# BaseBoard.net
KiCad netlist of a schematic drawn in Altium Designer
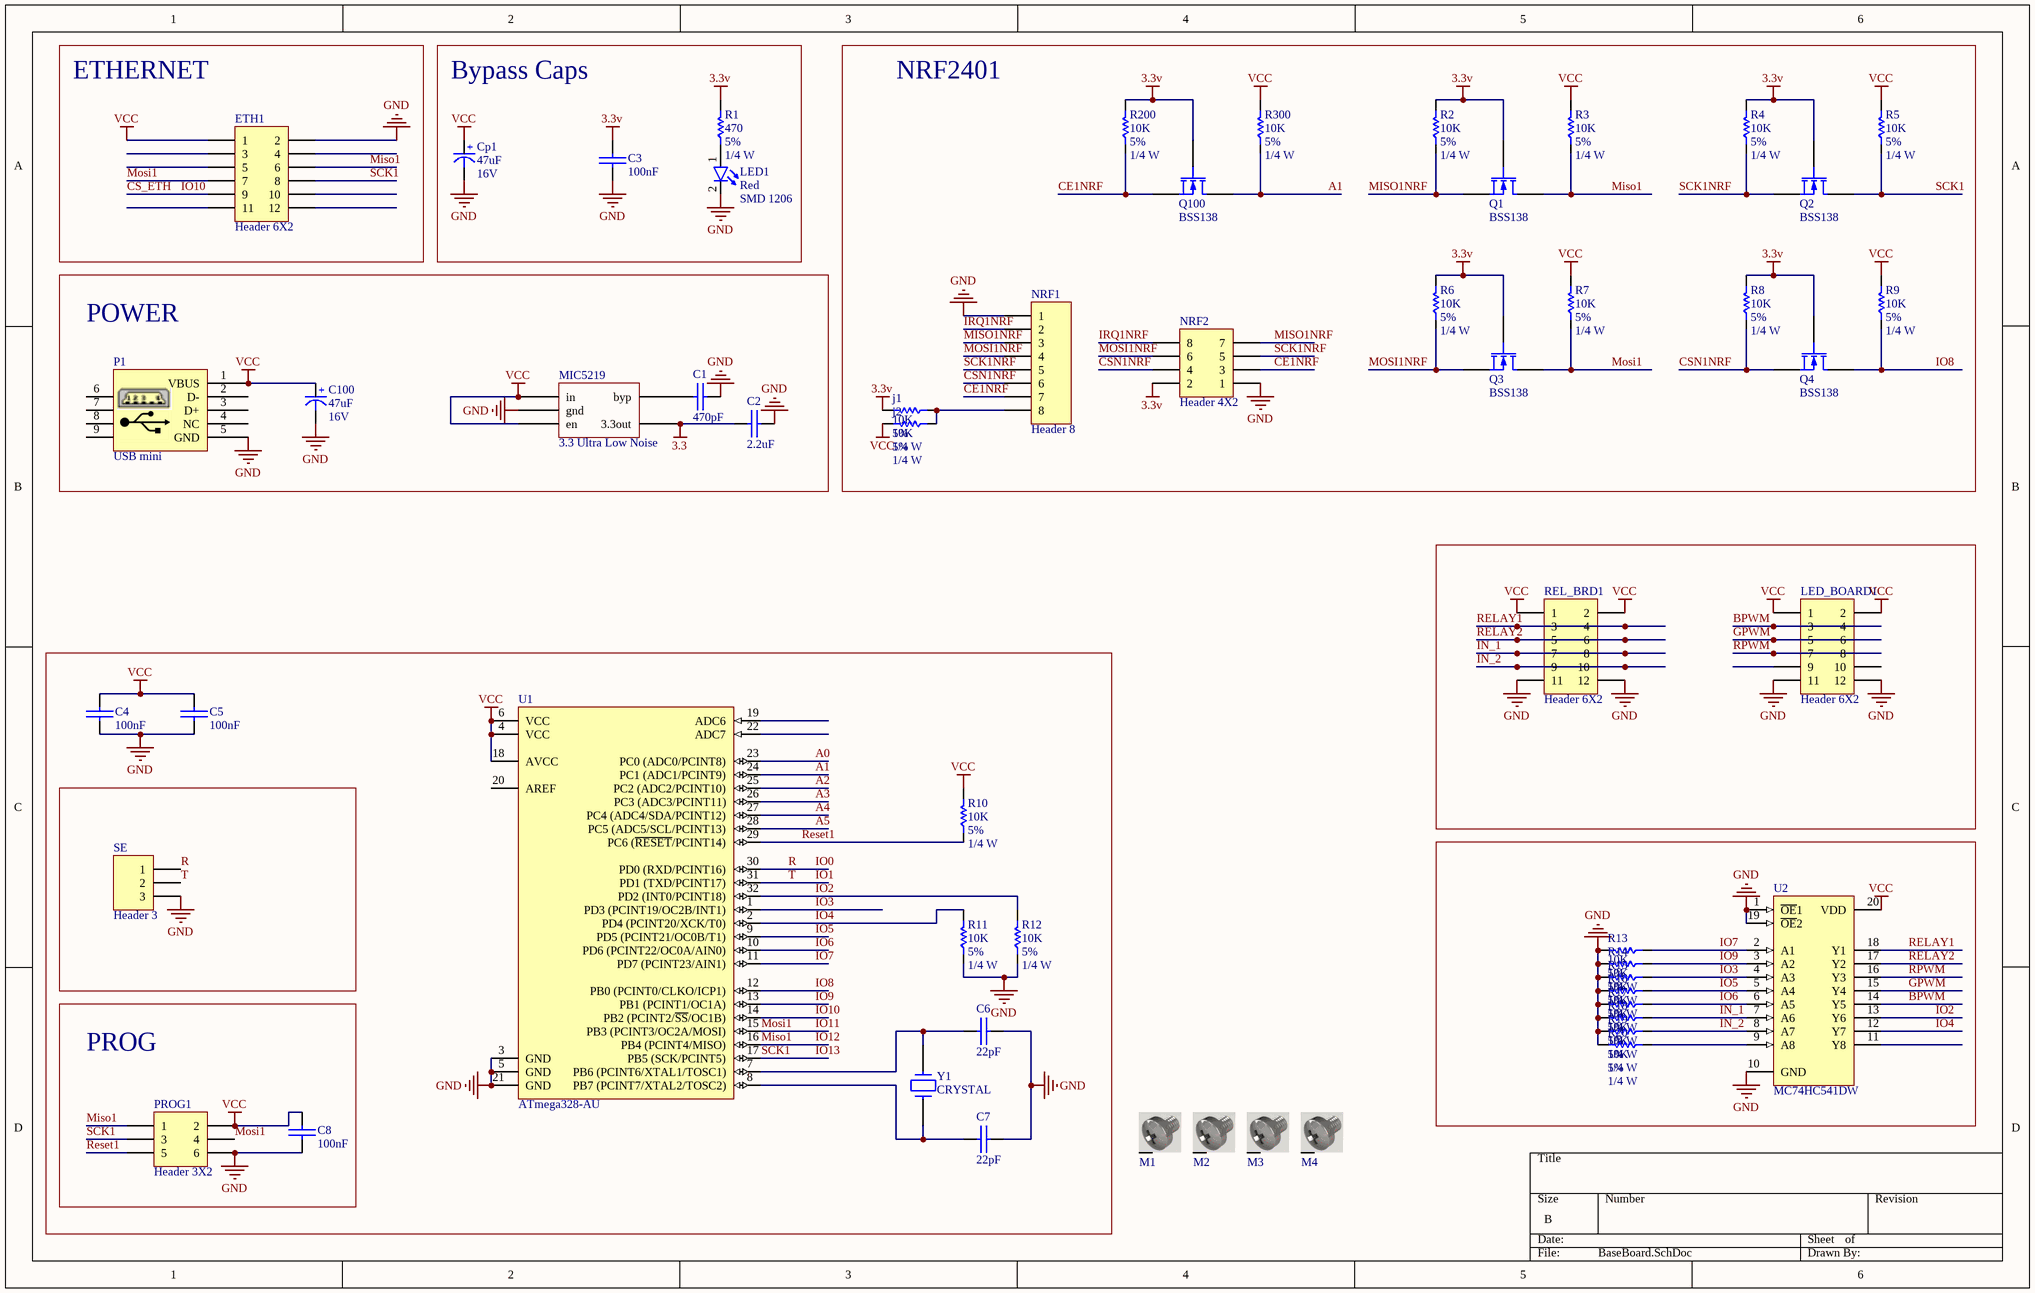
[diagram p0: BaseBoard.SchDoc]

(export (version "E")
  (design (tool "Eeschema 10.0.6"))
  (components
    (comp (ref "C1")
      (value "470pF")
      (footprint "SMD_CAP_0805")
      (description "Bipolar Capacitor")
      (fields (field (name "VOLTAGE") "100V") (field (name "DESIGNER") "Saeid Jorablo"))
      (libsource (lib "My Library") (part "Cap-Bipolar"))
    )
    (comp (ref "C2")
      (value "2.2uF")
      (footprint "SMD_CAP_1206")
      (description "Bipolar Capacitor")
      (fields (field (name "VOLTAGE") "100V") (field (name "DESIGNER") "Saeid Jorablo"))
      (libsource (lib "My Library") (part "Cap-Bipolar"))
    )
    (comp (ref "C3")
      (value "100nF")
      (footprint "CAPP 1206 (3216X18L) Size A")
      (description "Bipolar Capacitor")
      (fields (field (name "VOLTAGE") "100V") (field (name "DESIGNER") "Saeid Jorablo"))
      (libsource (lib "My Library") (part "Cap-Bipolar"))
    )
    (comp (ref "C4")
      (value "100nF")
      (footprint "CAPP 1206 (3216X18L) Size A")
      (description "Bipolar Capacitor")
      (fields (field (name "VOLTAGE") "100V") (field (name "DESIGNER") "Saeid Jorablo"))
      (libsource (lib "My Library") (part "Cap-Bipolar"))
    )
    (comp (ref "C5")
      (value "100nF")
      (footprint "CAPP 1206 (3216X18L) Size A")
      (description "Bipolar Capacitor")
      (fields (field (name "VOLTAGE") "100V") (field (name "DESIGNER") "Saeid Jorablo"))
      (libsource (lib "My Library") (part "Cap-Bipolar"))
    )
    (comp (ref "C6")
      (value "22pF")
      (footprint "CAPP 1206 (3216X18L) Size A")
      (description "Bipolar Capacitor")
      (fields (field (name "VOLTAGE") "100V") (field (name "DESIGNER") "Saeid Jorablo"))
      (libsource (lib "My Library") (part "Cap-Bipolar"))
    )
    (comp (ref "C7")
      (value "22pF")
      (footprint "CAPP 1206 (3216X18L) Size A")
      (description "Bipolar Capacitor")
      (fields (field (name "VOLTAGE") "100V") (field (name "DESIGNER") "Saeid Jorablo"))
      (libsource (lib "My Library") (part "Cap-Bipolar"))
    )
    (comp (ref "C8")
      (value "100nF")
      (footprint "CAPP 1206 (3216X18L) Size A")
      (description "Bipolar Capacitor")
      (fields (field (name "VOLTAGE") "100V") (field (name "DESIGNER") "Saeid Jorablo"))
      (libsource (lib "My Library") (part "Cap-Bipolar"))
    )
    (comp (ref "C100")
      (value "47uF")
      (footprint "CAPP 1206 (3216X18L) Size A")
      (description "Polar Capacitor")
      (fields (field (name "VOLTAGE") "16V") (field (name "DESIGNER") "Saeid Jorablo"))
      (libsource (lib "My Library") (part "Cap-Polar"))
    )
    (comp (ref "Cp1")
      (value "47uF")
      (footprint "CAPP 1206 (3216X18L) Size A")
      (description "Polar Capacitor")
      (fields (field (name "VOLTAGE") "16V") (field (name "DESIGNER") "Saeid Jorablo"))
      (libsource (lib "My Library") (part "Cap-Polar"))
    )
    (comp (ref "ETH1")
      (value "Header 6X2")
      (footprint "HDR2X6")
      (description "Header, 6-Pin, Dual row")
      (fields (field (name "PUBLISHER") "Altium Limited"))
      (libsource (lib "Miscellaneous Connectors") (part "Header 6X2"))
    )
    (comp (ref "j1")
      (value "10K")
      (footprint "RES 1206 (3216X08L)")
      (description "Resistor")
      (fields (field (name "TOLERANCE") "5%") (field (name "POWER") "1/4 W"))
      (libsource (lib "My Library") (part "Resistor"))
    )
    (comp (ref "j2")
      (value "10K")
      (footprint "RES 1206 (3216X08L)")
      (description "Resistor")
      (fields (field (name "TOLERANCE") "5%") (field (name "POWER") "1/4 W"))
      (libsource (lib "My Library") (part "Resistor"))
    )
    (comp (ref "LED1")
      (value "Red")
      (footprint "LED SMD 1206")
      (description "LED")
      (fields
        (field (name "COLOR") "Red")
        (field (name "SIZE") "SMD 1206")
        (field (name "DESIGNER") "Saeid Jorablo")
      )
      (libsource (lib "My Library") (part "LED"))
    )
    (comp (ref "LED_BOARD1")
      (value "Header 6X2")
      (footprint "HDR2X6")
      (description "Header, 6-Pin, Dual row")
      (fields (field (name "PUBLISHER") "Altium Limited"))
      (libsource (lib "Miscellaneous Connectors") (part "Header 6X2"))
    )
    (comp (ref "M1")
      (value "Screw")
      (footprint "Board Screw_No Silk")
      (description "Board Screw With Spacer")
      (libsource (lib "My Library") (part "Board Screw"))
    )
    (comp (ref "M2")
      (value "Screw")
      (footprint "Board Screw_No Silk")
      (description "Board Screw With Spacer")
      (libsource (lib "My Library") (part "Board Screw"))
    )
    (comp (ref "M3")
      (value "Screw")
      (footprint "Board Screw_No Silk")
      (description "Board Screw With Spacer")
      (libsource (lib "My Library") (part "Board Screw"))
    )
    (comp (ref "M4")
      (value "Screw")
      (footprint "Board Screw_No Silk")
      (description "Board Screw With Spacer")
      (libsource (lib "My Library") (part "Board Screw"))
    )
    (comp (ref "MIC5219")
      (value "3.3 Ultra Low Noise")
      (footprint "mic5205")
      (libsource (lib "mic5205") (part "Component_1"))
    )
    (comp (ref "NRF1")
      (value "Header 8")
      (footprint "HDR1X8")
      (description "Header, 8-Pin")
      (fields (field (name "PUBLISHER") "Altium Limited"))
      (libsource (lib "Miscellaneous Connectors") (part "Header 8"))
    )
    (comp (ref "NRF2")
      (value "Header 4X2")
      (footprint "HDR2X4")
      (description "Header, 4-Pin, Dual row")
      (fields (field (name "PUBLISHER") "Altium Limited"))
      (libsource (lib "Miscellaneous Connectors") (part "Header 4X2"))
    )
    (comp (ref "P1")
      (value "USB mini")
      (footprint "USB/SM0.8-6H5")
      (description "mini USB Connector")
      (libsource (lib "My Library") (part "USB mini"))
    )
    (comp (ref "PROG1")
      (value "Header 3X2")
      (footprint "HDR2X3")
      (description "Header, 3-Pin, Dual row")
      (fields (field (name "PUBLISHER") "Altium Limited"))
      (libsource (lib "Miscellaneous Connectors") (part "Header 3X2"))
    )
    (comp (ref "Q1")
      (value "BSS138")
      (footprint "SOT23")
      (description "N-Channel Enhancement Mode Vertical DMOS FET")
      (fields (field (name "PUBLISHER") "Altium Limited"))
      (libsource (lib "Zetex Discrete MOSFET") (part "BSS138"))
    )
    (comp (ref "Q2")
      (value "BSS138")
      (footprint "SOT23")
      (description "N-Channel Enhancement Mode Vertical DMOS FET")
      (fields (field (name "PUBLISHER") "Altium Limited"))
      (libsource (lib "Zetex Discrete MOSFET") (part "BSS138"))
    )
    (comp (ref "Q3")
      (value "BSS138")
      (footprint "SOT23")
      (description "N-Channel Enhancement Mode Vertical DMOS FET")
      (fields (field (name "PUBLISHER") "Altium Limited"))
      (libsource (lib "Zetex Discrete MOSFET") (part "BSS138"))
    )
    (comp (ref "Q4")
      (value "BSS138")
      (footprint "SOT23")
      (description "N-Channel Enhancement Mode Vertical DMOS FET")
      (fields (field (name "PUBLISHER") "Altium Limited"))
      (libsource (lib "Zetex Discrete MOSFET") (part "BSS138"))
    )
    (comp (ref "Q100")
      (value "BSS138")
      (footprint "SOT23")
      (description "N-Channel Enhancement Mode Vertical DMOS FET")
      (fields (field (name "PUBLISHER") "Altium Limited"))
      (libsource (lib "Zetex Discrete MOSFET") (part "BSS138"))
    )
    (comp (ref "R1")
      (value "470")
      (footprint "RES 1206 (3216X08L)")
      (description "Resistor")
      (fields (field (name "TOLERANCE") "5%") (field (name "POWER") "1/4 W"))
      (libsource (lib "My Library") (part "Resistor"))
    )
    (comp (ref "R2")
      (value "10K")
      (footprint "RES 1206 (3216X08L)")
      (description "Resistor")
      (fields (field (name "TOLERANCE") "5%") (field (name "POWER") "1/4 W"))
      (libsource (lib "My Library") (part "Resistor"))
    )
    (comp (ref "R3")
      (value "10K")
      (footprint "RES 1206 (3216X08L)")
      (description "Resistor")
      (fields (field (name "TOLERANCE") "5%") (field (name "POWER") "1/4 W"))
      (libsource (lib "My Library") (part "Resistor"))
    )
    (comp (ref "R4")
      (value "10K")
      (footprint "RES 1206 (3216X08L)")
      (description "Resistor")
      (fields (field (name "TOLERANCE") "5%") (field (name "POWER") "1/4 W"))
      (libsource (lib "My Library") (part "Resistor"))
    )
    (comp (ref "R5")
      (value "10K")
      (footprint "RES 1206 (3216X08L)")
      (description "Resistor")
      (fields (field (name "TOLERANCE") "5%") (field (name "POWER") "1/4 W"))
      (libsource (lib "My Library") (part "Resistor"))
    )
    (comp (ref "R6")
      (value "10K")
      (footprint "RES 1206 (3216X08L)")
      (description "Resistor")
      (fields (field (name "TOLERANCE") "5%") (field (name "POWER") "1/4 W"))
      (libsource (lib "My Library") (part "Resistor"))
    )
    (comp (ref "R7")
      (value "10K")
      (footprint "RES 1206 (3216X08L)")
      (description "Resistor")
      (fields (field (name "TOLERANCE") "5%") (field (name "POWER") "1/4 W"))
      (libsource (lib "My Library") (part "Resistor"))
    )
    (comp (ref "R8")
      (value "10K")
      (footprint "RES 1206 (3216X08L)")
      (description "Resistor")
      (fields (field (name "TOLERANCE") "5%") (field (name "POWER") "1/4 W"))
      (libsource (lib "My Library") (part "Resistor"))
    )
    (comp (ref "R9")
      (value "10K")
      (footprint "RES 1206 (3216X08L)")
      (description "Resistor")
      (fields (field (name "TOLERANCE") "5%") (field (name "POWER") "1/4 W"))
      (libsource (lib "My Library") (part "Resistor"))
    )
    (comp (ref "R10")
      (value "10K")
      (footprint "RES 1206 (3216X08L)")
      (description "Resistor")
      (fields (field (name "TOLERANCE") "5%") (field (name "POWER") "1/4 W"))
      (libsource (lib "My Library") (part "Resistor"))
    )
    (comp (ref "R11")
      (value "10K")
      (footprint "RES 1206 (3216X08L)")
      (description "Resistor")
      (fields (field (name "TOLERANCE") "5%") (field (name "POWER") "1/4 W"))
      (libsource (lib "My Library") (part "Resistor"))
    )
    (comp (ref "R12")
      (value "10K")
      (footprint "RES 1206 (3216X08L)")
      (description "Resistor")
      (fields (field (name "TOLERANCE") "5%") (field (name "POWER") "1/4 W"))
      (libsource (lib "My Library") (part "Resistor"))
    )
    (comp (ref "R13")
      (value "10K")
      (footprint "RES 1206 (3216X08L)")
      (description "Resistor")
      (fields (field (name "TOLERANCE") "5%") (field (name "POWER") "1/4 W"))
      (libsource (lib "My Library") (part "Resistor"))
    )
    (comp (ref "R14")
      (value "10K")
      (footprint "RES 1206 (3216X08L)")
      (description "Resistor")
      (fields (field (name "TOLERANCE") "5%") (field (name "POWER") "1/4 W"))
      (libsource (lib "My Library") (part "Resistor"))
    )
    (comp (ref "R15")
      (value "10K")
      (footprint "RES 1206 (3216X08L)")
      (description "Resistor")
      (fields (field (name "TOLERANCE") "5%") (field (name "POWER") "1/4 W"))
      (libsource (lib "My Library") (part "Resistor"))
    )
    (comp (ref "R16")
      (value "10K")
      (footprint "RES 1206 (3216X08L)")
      (description "Resistor")
      (fields (field (name "TOLERANCE") "5%") (field (name "POWER") "1/4 W"))
      (libsource (lib "My Library") (part "Resistor"))
    )
    (comp (ref "R17")
      (value "10K")
      (footprint "RES 1206 (3216X08L)")
      (description "Resistor")
      (fields (field (name "TOLERANCE") "5%") (field (name "POWER") "1/4 W"))
      (libsource (lib "My Library") (part "Resistor"))
    )
    (comp (ref "R18")
      (value "10K")
      (footprint "RES 1206 (3216X08L)")
      (description "Resistor")
      (fields (field (name "TOLERANCE") "5%") (field (name "POWER") "1/4 W"))
      (libsource (lib "My Library") (part "Resistor"))
    )
    (comp (ref "R19")
      (value "10K")
      (footprint "RES 1206 (3216X08L)")
      (description "Resistor")
      (fields (field (name "TOLERANCE") "5%") (field (name "POWER") "1/4 W"))
      (libsource (lib "My Library") (part "Resistor"))
    )
    (comp (ref "R20")
      (value "10K")
      (footprint "RES 1206 (3216X08L)")
      (description "Resistor")
      (fields (field (name "TOLERANCE") "5%") (field (name "POWER") "1/4 W"))
      (libsource (lib "My Library") (part "Resistor"))
    )
    (comp (ref "R200")
      (value "10K")
      (footprint "RES 1206 (3216X08L)")
      (description "Resistor")
      (fields (field (name "TOLERANCE") "5%") (field (name "POWER") "1/4 W"))
      (libsource (lib "My Library") (part "Resistor"))
    )
    (comp (ref "R300")
      (value "10K")
      (footprint "RES 1206 (3216X08L)")
      (description "Resistor")
      (fields (field (name "TOLERANCE") "5%") (field (name "POWER") "1/4 W"))
      (libsource (lib "My Library") (part "Resistor"))
    )
    (comp (ref "REL_BRD1")
      (value "Header 6X2")
      (footprint "HDR2X6")
      (description "Header, 6-Pin, Dual row")
      (fields (field (name "PUBLISHER") "Altium Limited"))
      (libsource (lib "Miscellaneous Connectors") (part "Header 6X2"))
    )
    (comp (ref "SE")
      (value "Header 3")
      (footprint "HDR1X3")
      (description "Header, 3-Pin")
      (fields (field (name "PUBLISHER") "Altium Limited"))
      (libsource (lib "Miscellaneous Connectors") (part "Header 3"))
    )
    (comp (ref "U1")
      (value "ATmega328-AU")
      (footprint "32A_N")
      (fields (field (name "PUBLISHER") "Altium Limited"))
      (libsource (lib "Atmel Microcontroller 8-Bit megaAVR") (part "ATmega328-AU"))
    )
    (comp (ref "U2")
      (value "MC74HC541DW")
      (footprint "751D-03_N")
      (description "Octal 3-State Non-Inverting Buffer/Line Driver/Line Receiver")
      (fields (field (name "PUBLISHER") "Altium Limited"))
      (libsource (lib "Motorola Logic Buffer Line Driver") (part "MC74HC541DW"))
    )
    (comp (ref "Y1")
      (value "CRYSTAL")
      (footprint "My_Crystal")
      (description "Crystal")
      (libsource (lib "Mylib") (part "CRYSTAL"))
    )
  )
  (nets
    (net (code "1") (name "/A0") (class "Default")
      (node (ref "U1") (pin "23") (pinfunction "PC0_(ADC0/PCINT8)_23") (pintype "bidirectional"))
    )
    (net (code "2") (name "/A1") (class "Default")
      (node (ref "Q100") (pin "1") (pinfunction "D_1") (pintype "passive"))
      (node (ref "R300") (pin "1") (pinfunction "1_1") (pintype "passive"))
      (node (ref "U1") (pin "24") (pinfunction "PC1_(ADC1/PCINT9)_24") (pintype "bidirectional"))
    )
    (net (code "3") (name "/A2") (class "Default")
      (node (ref "U1") (pin "25") (pinfunction "PC2_(ADC2/PCINT10)_25") (pintype "bidirectional"))
    )
    (net (code "4") (name "/A3") (class "Default")
      (node (ref "U1") (pin "26") (pinfunction "PC3_(ADC3/PCINT11)_26") (pintype "bidirectional"))
    )
    (net (code "5") (name "/A4") (class "Default")
      (node (ref "U1") (pin "27") (pinfunction "PC4_(ADC4/SDA/PCINT12)_27") (pintype "bidirectional"))
    )
    (net (code "6") (name "/A5") (class "Default")
      (node (ref "U1") (pin "28") (pinfunction "PC5_(ADC5/SCL/PCINT13)_28") (pintype "bidirectional"))
    )
    (net (code "7") (name "/BPWM") (class "Default")
      (node (ref "LED_BOARD1") (pin "3") (pinfunction "3_3") (pintype "passive"))
      (node (ref "LED_BOARD1") (pin "4") (pinfunction "4_4") (pintype "passive"))
      (node (ref "U2") (pin "14") (pinfunction "Y5_14") (pintype "tri_state"))
    )
    (net (code "8") (name "/CE1NRF") (class "Default")
      (node (ref "NRF1") (pin "7") (pinfunction "7_7") (pintype "passive"))
      (node (ref "NRF2") (pin "3") (pinfunction "3_3") (pintype "passive"))
      (node (ref "Q100") (pin "2") (pinfunction "S_2") (pintype "passive"))
      (node (ref "R200") (pin "1") (pinfunction "1_1") (pintype "passive"))
    )
    (net (code "9") (name "/CSN1NRF") (class "Default")
      (node (ref "NRF1") (pin "6") (pinfunction "6_6") (pintype "passive"))
      (node (ref "NRF2") (pin "4") (pinfunction "4_4") (pintype "passive"))
      (node (ref "Q4") (pin "2") (pinfunction "S_2") (pintype "passive"))
      (node (ref "R8") (pin "1") (pinfunction "1_1") (pintype "passive"))
    )
    (net (code "10") (name "/CS_ETH") (class "Default")
      (node (ref "ETH1") (pin "9") (pinfunction "9_9") (pintype "passive"))
      (node (ref "U1") (pin "14") (pinfunction "PB2_(PCINT2/~{SS}/OC1B)_14") (pintype "bidirectional"))
    )
    (net (code "11") (name "/GPWM") (class "Default")
      (node (ref "LED_BOARD1") (pin "5") (pinfunction "5_5") (pintype "passive"))
      (node (ref "LED_BOARD1") (pin "6") (pinfunction "6_6") (pintype "passive"))
      (node (ref "U2") (pin "15") (pinfunction "Y4_15") (pintype "tri_state"))
    )
    (net (code "12") (name "/IN_1") (class "Default")
      (node (ref "R18") (pin "1") (pinfunction "1_1") (pintype "passive"))
      (node (ref "REL_BRD1") (pin "7") (pinfunction "7_7") (pintype "passive"))
      (node (ref "REL_BRD1") (pin "8") (pinfunction "8_8") (pintype "passive"))
      (node (ref "U2") (pin "7") (pinfunction "A6_7") (pintype "input"))
    )
    (net (code "13") (name "/IN_2") (class "Default")
      (node (ref "R19") (pin "1") (pinfunction "1_1") (pintype "passive"))
      (node (ref "REL_BRD1") (pin "10") (pinfunction "10_10") (pintype "passive"))
      (node (ref "REL_BRD1") (pin "9") (pinfunction "9_9") (pintype "passive"))
      (node (ref "U2") (pin "8") (pinfunction "A7_8") (pintype "input"))
    )
    (net (code "14") (name "/IO0") (class "Default")
      (node (ref "SE") (pin "1") (pinfunction "1_1") (pintype "passive"))
      (node (ref "U1") (pin "30") (pinfunction "PD0_(RXD/PCINT16)_30") (pintype "bidirectional"))
    )
    (net (code "15") (name "/IO1") (class "Default")
      (node (ref "SE") (pin "2") (pinfunction "2_2") (pintype "passive"))
      (node (ref "U1") (pin "31") (pinfunction "PD1_(TXD/PCINT17)_31") (pintype "bidirectional"))
    )
    (net (code "16") (name "/IO2") (class "Default")
      (node (ref "R12") (pin "2") (pinfunction "2_2") (pintype "passive"))
      (node (ref "U1") (pin "32") (pinfunction "PD2_(INT0/PCINT18)_32") (pintype "bidirectional"))
      (node (ref "U2") (pin "13") (pinfunction "Y6_13") (pintype "tri_state"))
    )
    (net (code "17") (name "/IO3") (class "Default")
      (node (ref "R15") (pin "1") (pinfunction "1_1") (pintype "passive"))
      (node (ref "U1") (pin "1") (pinfunction "PD3_(PCINT19/OC2B/INT1)_1") (pintype "bidirectional"))
      (node (ref "U2") (pin "4") (pinfunction "A3_4") (pintype "input"))
    )
    (net (code "18") (name "/IO4") (class "Default")
      (node (ref "R11") (pin "2") (pinfunction "2_2") (pintype "passive"))
      (node (ref "U1") (pin "2") (pinfunction "PD4_(PCINT20/XCK/T0)_2") (pintype "bidirectional"))
      (node (ref "U2") (pin "12") (pinfunction "Y7_12") (pintype "tri_state"))
    )
    (net (code "19") (name "/IO5") (class "Default")
      (node (ref "R16") (pin "1") (pinfunction "1_1") (pintype "passive"))
      (node (ref "U1") (pin "9") (pinfunction "PD5_(PCINT21/OC0B/T1)_9") (pintype "bidirectional"))
      (node (ref "U2") (pin "5") (pinfunction "A4_5") (pintype "input"))
    )
    (net (code "20") (name "/IO6") (class "Default")
      (node (ref "R17") (pin "1") (pinfunction "1_1") (pintype "passive"))
      (node (ref "U1") (pin "10") (pinfunction "PD6_(PCINT22/OC0A/AIN0)_10") (pintype "bidirectional"))
      (node (ref "U2") (pin "6") (pinfunction "A5_6") (pintype "input"))
    )
    (net (code "21") (name "/IO7") (class "Default")
      (node (ref "R13") (pin "1") (pinfunction "1_1") (pintype "passive"))
      (node (ref "U1") (pin "11") (pinfunction "PD7_(PCINT23/AIN1)_11") (pintype "bidirectional"))
      (node (ref "U2") (pin "2") (pinfunction "A1_2") (pintype "input"))
    )
    (net (code "22") (name "/IO8") (class "Default")
      (node (ref "Q4") (pin "1") (pinfunction "D_1") (pintype "passive"))
      (node (ref "R9") (pin "1") (pinfunction "1_1") (pintype "passive"))
      (node (ref "U1") (pin "12") (pinfunction "PB0_(PCINT0/CLKO/ICP1)_12") (pintype "bidirectional"))
    )
    (net (code "23") (name "/IO9") (class "Default")
      (node (ref "R14") (pin "1") (pinfunction "1_1") (pintype "passive"))
      (node (ref "U1") (pin "13") (pinfunction "PB1_(PCINT1/OC1A)_13") (pintype "bidirectional"))
      (node (ref "U2") (pin "3") (pinfunction "A2_3") (pintype "input"))
    )
    (net (code "24") (name "/IO11") (class "Default")
      (node (ref "ETH1") (pin "7") (pinfunction "7_7") (pintype "passive"))
      (node (ref "PROG1") (pin "4") (pinfunction "4_4") (pintype "passive"))
      (node (ref "Q3") (pin "1") (pinfunction "D_1") (pintype "passive"))
      (node (ref "R7") (pin "1") (pinfunction "1_1") (pintype "passive"))
      (node (ref "U1") (pin "15") (pinfunction "PB3_(PCINT3/OC2A/MOSI)_15") (pintype "bidirectional"))
    )
    (net (code "25") (name "/IO12") (class "Default")
      (node (ref "ETH1") (pin "6") (pinfunction "6_6") (pintype "passive"))
      (node (ref "PROG1") (pin "1") (pinfunction "1_1") (pintype "passive"))
      (node (ref "Q1") (pin "1") (pinfunction "D_1") (pintype "passive"))
      (node (ref "R3") (pin "1") (pinfunction "1_1") (pintype "passive"))
      (node (ref "U1") (pin "16") (pinfunction "PB4_(PCINT4/MISO)_16") (pintype "bidirectional"))
    )
    (net (code "26") (name "/IO13") (class "Default")
      (node (ref "ETH1") (pin "8") (pinfunction "8_8") (pintype "passive"))
      (node (ref "PROG1") (pin "3") (pinfunction "3_3") (pintype "passive"))
      (node (ref "Q2") (pin "1") (pinfunction "D_1") (pintype "passive"))
      (node (ref "R5") (pin "1") (pinfunction "1_1") (pintype "passive"))
      (node (ref "U1") (pin "17") (pinfunction "PB5_(SCK/PCINT5)_17") (pintype "bidirectional"))
    )
    (net (code "27") (name "/IRQ1NRF") (class "Default")
      (node (ref "NRF1") (pin "2") (pinfunction "2_2") (pintype "passive"))
      (node (ref "NRF2") (pin "8") (pinfunction "8_8") (pintype "passive"))
    )
    (net (code "28") (name "/MISO1NRF") (class "Default")
      (node (ref "NRF1") (pin "3") (pinfunction "3_3") (pintype "passive"))
      (node (ref "NRF2") (pin "7") (pinfunction "7_7") (pintype "passive"))
      (node (ref "Q1") (pin "2") (pinfunction "S_2") (pintype "passive"))
      (node (ref "R2") (pin "1") (pinfunction "1_1") (pintype "passive"))
    )
    (net (code "29") (name "/MOSI1NRF") (class "Default")
      (node (ref "NRF1") (pin "4") (pinfunction "4_4") (pintype "passive"))
      (node (ref "NRF2") (pin "6") (pinfunction "6_6") (pintype "passive"))
      (node (ref "Q3") (pin "2") (pinfunction "S_2") (pintype "passive"))
      (node (ref "R6") (pin "1") (pinfunction "1_1") (pintype "passive"))
    )
    (net (code "30") (name "/RELAY1") (class "Default")
      (node (ref "REL_BRD1") (pin "3") (pinfunction "3_3") (pintype "passive"))
      (node (ref "REL_BRD1") (pin "4") (pinfunction "4_4") (pintype "passive"))
      (node (ref "U2") (pin "18") (pinfunction "Y1_18") (pintype "tri_state"))
    )
    (net (code "31") (name "/RELAY2") (class "Default")
      (node (ref "REL_BRD1") (pin "5") (pinfunction "5_5") (pintype "passive"))
      (node (ref "REL_BRD1") (pin "6") (pinfunction "6_6") (pintype "passive"))
      (node (ref "U2") (pin "17") (pinfunction "Y2_17") (pintype "tri_state"))
    )
    (net (code "32") (name "/RPWM") (class "Default")
      (node (ref "LED_BOARD1") (pin "7") (pinfunction "7_7") (pintype "passive"))
      (node (ref "LED_BOARD1") (pin "8") (pinfunction "8_8") (pintype "passive"))
      (node (ref "U2") (pin "16") (pinfunction "Y3_16") (pintype "tri_state"))
    )
    (net (code "33") (name "/Reset1") (class "Default")
      (node (ref "PROG1") (pin "5") (pinfunction "5_5") (pintype "passive"))
      (node (ref "R10") (pin "1") (pinfunction "1_1") (pintype "passive"))
      (node (ref "U1") (pin "29") (pinfunction "PC6_(~{RESET}/PCINT14)_29") (pintype "bidirectional"))
    )
    (net (code "34") (name "/SCK1NRF") (class "Default")
      (node (ref "NRF1") (pin "5") (pinfunction "5_5") (pintype "passive"))
      (node (ref "NRF2") (pin "5") (pinfunction "5_5") (pintype "passive"))
      (node (ref "Q2") (pin "2") (pinfunction "S_2") (pintype "passive"))
      (node (ref "R4") (pin "1") (pinfunction "1_1") (pintype "passive"))
    )
    (net (code "35") (name "3.3") (class "Default")
      (node (ref "C2") (pin "1") (pinfunction "+_1") (pintype "passive"))
      (node (ref "MIC5219") (pin "5") (pinfunction "3.3out_5") (pintype "passive"))
    )
    (net (code "36") (name "3.3v") (class "Default")
      (node (ref "C3") (pin "2") (pinfunction "-_2") (pintype "passive"))
      (node (ref "NRF2") (pin "2") (pinfunction "2_2") (pintype "passive"))
      (node (ref "Q1") (pin "3") (pinfunction "G_3") (pintype "passive"))
      (node (ref "Q100") (pin "3") (pinfunction "G_3") (pintype "passive"))
      (node (ref "Q2") (pin "3") (pinfunction "G_3") (pintype "passive"))
      (node (ref "Q3") (pin "3") (pinfunction "G_3") (pintype "passive"))
      (node (ref "Q4") (pin "3") (pinfunction "G_3") (pintype "passive"))
      (node (ref "R1") (pin "2") (pinfunction "2_2") (pintype "passive"))
      (node (ref "R2") (pin "2") (pinfunction "2_2") (pintype "passive"))
      (node (ref "R200") (pin "2") (pinfunction "2_2") (pintype "passive"))
      (node (ref "R4") (pin "2") (pinfunction "2_2") (pintype "passive"))
      (node (ref "R6") (pin "2") (pinfunction "2_2") (pintype "passive"))
      (node (ref "R8") (pin "2") (pinfunction "2_2") (pintype "passive"))
      (node (ref "j1") (pin "2") (pinfunction "2_2") (pintype "passive"))
    )
    (net (code "37") (name "GND") (class "Default")
      (node (ref "C1") (pin "2") (pinfunction "-_2") (pintype "passive"))
      (node (ref "C100") (pin "2") (pinfunction "-_2") (pintype "passive"))
      (node (ref "C2") (pin "2") (pinfunction "-_2") (pintype "passive"))
      (node (ref "C3") (pin "1") (pinfunction "+_1") (pintype "passive"))
      (node (ref "C4") (pin "1") (pinfunction "+_1") (pintype "passive"))
      (node (ref "C5") (pin "1") (pinfunction "+_1") (pintype "passive"))
      (node (ref "C6") (pin "2") (pinfunction "-_2") (pintype "passive"))
      (node (ref "C7") (pin "1") (pinfunction "+_1") (pintype "passive"))
      (node (ref "C8") (pin "1") (pinfunction "+_1") (pintype "passive"))
      (node (ref "Cp1") (pin "2") (pinfunction "-_2") (pintype "passive"))
      (node (ref "ETH1") (pin "2") (pinfunction "2_2") (pintype "passive"))
      (node (ref "LED1") (pin "2") (pinfunction "K_2") (pintype "passive"))
      (node (ref "LED_BOARD1") (pin "11") (pinfunction "11_11") (pintype "passive"))
      (node (ref "LED_BOARD1") (pin "12") (pinfunction "12_12") (pintype "passive"))
      (node (ref "MIC5219") (pin "2") (pinfunction "gnd_2") (pintype "passive"))
      (node (ref "NRF1") (pin "1") (pinfunction "1_1") (pintype "passive"))
      (node (ref "NRF2") (pin "1") (pinfunction "1_1") (pintype "passive"))
      (node (ref "P1") (pin "5") (pinfunction "GND_5") (pintype "power_in"))
      (node (ref "PROG1") (pin "6") (pinfunction "6_6") (pintype "passive"))
      (node (ref "R11") (pin "1") (pinfunction "1_1") (pintype "passive"))
      (node (ref "R12") (pin "1") (pinfunction "1_1") (pintype "passive"))
      (node (ref "R13") (pin "2") (pinfunction "2_2") (pintype "passive"))
      (node (ref "R14") (pin "2") (pinfunction "2_2") (pintype "passive"))
      (node (ref "R15") (pin "2") (pinfunction "2_2") (pintype "passive"))
      (node (ref "R16") (pin "2") (pinfunction "2_2") (pintype "passive"))
      (node (ref "R17") (pin "2") (pinfunction "2_2") (pintype "passive"))
      (node (ref "R18") (pin "2") (pinfunction "2_2") (pintype "passive"))
      (node (ref "R19") (pin "2") (pinfunction "2_2") (pintype "passive"))
      (node (ref "R20") (pin "2") (pinfunction "2_2") (pintype "passive"))
      (node (ref "REL_BRD1") (pin "11") (pinfunction "11_11") (pintype "passive"))
      (node (ref "REL_BRD1") (pin "12") (pinfunction "12_12") (pintype "passive"))
      (node (ref "SE") (pin "3") (pinfunction "3_3") (pintype "passive"))
      (node (ref "U1") (pin "21") (pinfunction "GND_21") (pintype "power_in"))
      (node (ref "U1") (pin "3") (pinfunction "GND_3") (pintype "power_in"))
      (node (ref "U1") (pin "5") (pinfunction "GND_5") (pintype "power_in"))
      (node (ref "U2") (pin "1") (pinfunction "~{OE}1_1") (pintype "input"))
      (node (ref "U2") (pin "10") (pinfunction "GND_10") (pintype "power_in"))
      (node (ref "U2") (pin "19") (pinfunction "~{OE}2_19") (pintype "input"))
    )
    (net (code "38") (name "Net-(C1-+)") (class "Default")
      (node (ref "C1") (pin "1") (pinfunction "+_1") (pintype "passive"))
      (node (ref "MIC5219") (pin "4") (pinfunction "byp_4") (pintype "passive"))
    )
    (net (code "39") (name "Net-(C6-+)") (class "Default")
      (node (ref "C6") (pin "1") (pinfunction "+_1") (pintype "passive"))
      (node (ref "U1") (pin "7") (pinfunction "PB6_(PCINT6/XTAL1/TOSC1)_7") (pintype "bidirectional"))
      (node (ref "Y1") (pin "2") (pinfunction "2_2") (pintype "passive"))
    )
    (net (code "40") (name "Net-(C7--)") (class "Default")
      (node (ref "C7") (pin "2") (pinfunction "-_2") (pintype "passive"))
      (node (ref "U1") (pin "8") (pinfunction "PB7_(PCINT7/XTAL2/TOSC2)_8") (pintype "bidirectional"))
      (node (ref "Y1") (pin "1") (pinfunction "1_1") (pintype "passive"))
    )
    (net (code "41") (name "Net-(LED1-A)") (class "Default")
      (node (ref "LED1") (pin "1") (pinfunction "A_1") (pintype "passive"))
      (node (ref "R1") (pin "1") (pinfunction "1_1") (pintype "passive"))
    )
    (net (code "42") (name "Net-(NRF1-Pad8)") (class "Default")
      (node (ref "NRF1") (pin "8") (pinfunction "8_8") (pintype "passive"))
      (node (ref "j1") (pin "1") (pinfunction "1_1") (pintype "passive"))
      (node (ref "j2") (pin "1") (pinfunction "1_1") (pintype "passive"))
    )
    (net (code "43") (name "Net-(U2-A8)") (class "Default")
      (node (ref "R20") (pin "1") (pinfunction "1_1") (pintype "passive"))
      (node (ref "U2") (pin "9") (pinfunction "A8_9") (pintype "input"))
    )
    (net (code "44") (name "VCC") (class "Default")
      (node (ref "C100") (pin "1") (pinfunction "+_1") (pintype "passive"))
      (node (ref "C4") (pin "2") (pinfunction "-_2") (pintype "passive"))
      (node (ref "C5") (pin "2") (pinfunction "-_2") (pintype "passive"))
      (node (ref "C8") (pin "2") (pinfunction "-_2") (pintype "passive"))
      (node (ref "Cp1") (pin "1") (pinfunction "+_1") (pintype "passive"))
      (node (ref "ETH1") (pin "1") (pinfunction "1_1") (pintype "passive"))
      (node (ref "LED_BOARD1") (pin "1") (pinfunction "1_1") (pintype "passive"))
      (node (ref "LED_BOARD1") (pin "2") (pinfunction "2_2") (pintype "passive"))
      (node (ref "MIC5219") (pin "1") (pinfunction "in_1") (pintype "passive"))
      (node (ref "MIC5219") (pin "3") (pinfunction "en_3") (pintype "passive"))
      (node (ref "P1") (pin "1") (pinfunction "VBUS_1") (pintype "power_in"))
      (node (ref "PROG1") (pin "2") (pinfunction "2_2") (pintype "passive"))
      (node (ref "R10") (pin "2") (pinfunction "2_2") (pintype "passive"))
      (node (ref "R3") (pin "2") (pinfunction "2_2") (pintype "passive"))
      (node (ref "R300") (pin "2") (pinfunction "2_2") (pintype "passive"))
      (node (ref "R5") (pin "2") (pinfunction "2_2") (pintype "passive"))
      (node (ref "R7") (pin "2") (pinfunction "2_2") (pintype "passive"))
      (node (ref "R9") (pin "2") (pinfunction "2_2") (pintype "passive"))
      (node (ref "REL_BRD1") (pin "1") (pinfunction "1_1") (pintype "passive"))
      (node (ref "REL_BRD1") (pin "2") (pinfunction "2_2") (pintype "passive"))
      (node (ref "U1") (pin "18") (pinfunction "AVCC_18") (pintype "power_in"))
      (node (ref "U1") (pin "4") (pinfunction "VCC_4") (pintype "power_in"))
      (node (ref "U1") (pin "6") (pinfunction "VCC_6") (pintype "power_in"))
      (node (ref "U2") (pin "20") (pinfunction "VDD_20") (pintype "power_in"))
      (node (ref "j2") (pin "2") (pinfunction "2_2") (pintype "passive"))
    )
    (net (code "45") (name "unconnected-(ETH1-Pad3)") (class "Default")
      (node (ref "ETH1") (pin "3") (pinfunction "3_3") (pintype "passive"))
    )
    (net (code "46") (name "unconnected-(ETH1-Pad4)") (class "Default")
      (node (ref "ETH1") (pin "4") (pinfunction "4_4") (pintype "passive"))
    )
    (net (code "47") (name "unconnected-(ETH1-Pad5)") (class "Default")
      (node (ref "ETH1") (pin "5") (pinfunction "5_5") (pintype "passive"))
    )
    (net (code "48") (name "unconnected-(ETH1-Pad10)") (class "Default")
      (node (ref "ETH1") (pin "10") (pinfunction "10_10") (pintype "passive"))
    )
    (net (code "49") (name "unconnected-(ETH1-Pad11)") (class "Default")
      (node (ref "ETH1") (pin "11") (pinfunction "11_11") (pintype "passive"))
    )
    (net (code "50") (name "unconnected-(ETH1-Pad12)") (class "Default")
      (node (ref "ETH1") (pin "12") (pinfunction "12_12") (pintype "passive"))
    )
    (net (code "51") (name "unconnected-(LED_BOARD1-Pad9)") (class "Default")
      (node (ref "LED_BOARD1") (pin "9") (pinfunction "9_9") (pintype "passive"))
    )
    (net (code "52") (name "unconnected-(LED_BOARD1-Pad10)") (class "Default")
      (node (ref "LED_BOARD1") (pin "10") (pinfunction "10_10") (pintype "passive"))
    )
    (net (code "53") (name "unconnected-(M1-PadS)") (class "Default")
      (node (ref "M1") (pin "S") (pinfunction "S_S") (pintype "passive"))
    )
    (net (code "54") (name "unconnected-(M2-PadS)") (class "Default")
      (node (ref "M2") (pin "S") (pinfunction "S_S") (pintype "passive"))
    )
    (net (code "55") (name "unconnected-(M3-PadS)") (class "Default")
      (node (ref "M3") (pin "S") (pinfunction "S_S") (pintype "passive"))
    )
    (net (code "56") (name "unconnected-(M4-PadS)") (class "Default")
      (node (ref "M4") (pin "S") (pinfunction "S_S") (pintype "passive"))
    )
    (net (code "57") (name "unconnected-(P1-D+-Pad3)") (class "Default")
      (node (ref "P1") (pin "3") (pinfunction "D+_3") (pintype "passive"))
    )
    (net (code "58") (name "unconnected-(P1-D--Pad2)") (class "Default")
      (node (ref "P1") (pin "2") (pinfunction "D-_2") (pintype "passive"))
    )
    (net (code "59") (name "unconnected-(P1-NC-Pad4)") (class "Default")
      (node (ref "P1") (pin "4") (pinfunction "NC_4") (pintype "power_in"))
    )
    (net (code "60") (name "unconnected-(P1-Pad6)") (class "Default")
      (node (ref "P1") (pin "6") (pinfunction "6_6") (pintype "passive"))
    )
    (net (code "61") (name "unconnected-(P1-Pad7)") (class "Default")
      (node (ref "P1") (pin "7") (pinfunction "7_7") (pintype "passive"))
    )
    (net (code "62") (name "unconnected-(P1-Pad8)") (class "Default")
      (node (ref "P1") (pin "8") (pinfunction "8_8") (pintype "passive"))
    )
    (net (code "63") (name "unconnected-(P1-Pad9)") (class "Default")
      (node (ref "P1") (pin "9") (pinfunction "9_9") (pintype "passive"))
    )
    (net (code "64") (name "unconnected-(U1-ADC6-Pad19)") (class "Default")
      (node (ref "U1") (pin "19") (pinfunction "ADC6_19") (pintype "input"))
    )
    (net (code "65") (name "unconnected-(U1-ADC7-Pad22)") (class "Default")
      (node (ref "U1") (pin "22") (pinfunction "ADC7_22") (pintype "input"))
    )
    (net (code "66") (name "unconnected-(U1-AREF-Pad20)") (class "Default")
      (node (ref "U1") (pin "20") (pinfunction "AREF_20") (pintype "passive"))
    )
    (net (code "67") (name "unconnected-(U2-Y8-Pad11)") (class "Default")
      (node (ref "U2") (pin "11") (pinfunction "Y8_11") (pintype "tri_state"))
    )
  )
)
